# DDR3_Memory_Banks_32-33-34.net
KiCad netlist of a schematic drawn in Altium Designer
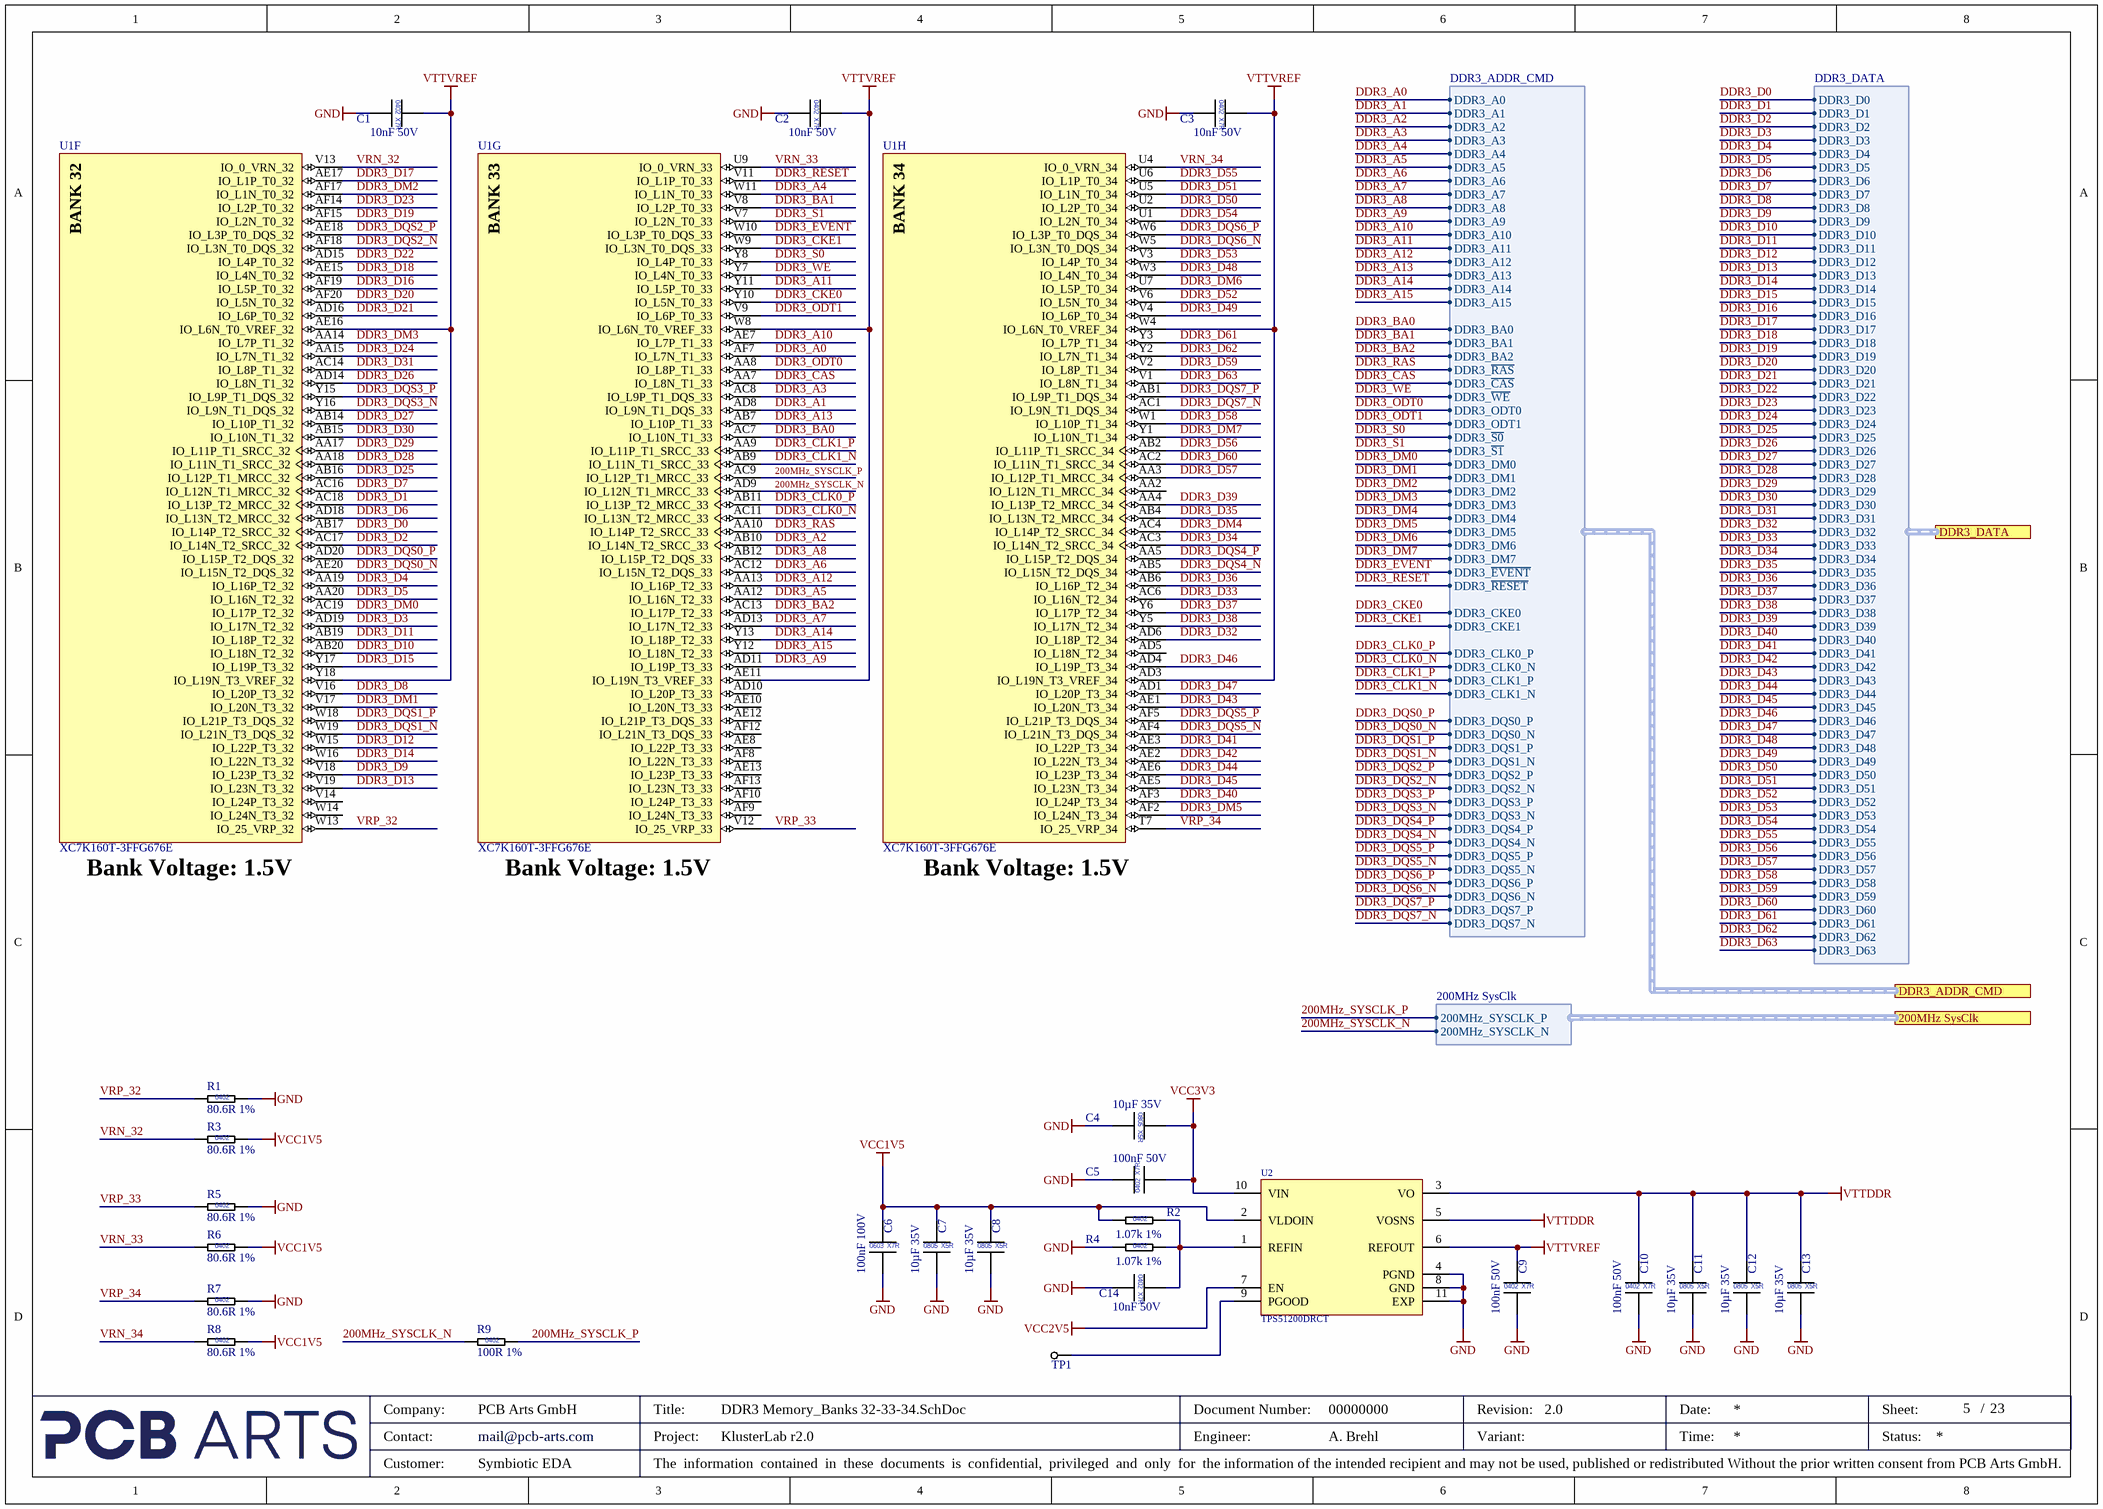
[diagram p0: DDR3 Memory_Banks 32-33-34.SchDoc]

(export (version "E")
  (design (tool "Eeschema 10.0.6"))
  (components
    (comp (ref "C1")
      (value "10nF 50V")
      (footprint "Cap:CAP_0402_L")
      (description "Multilayer Ceramic Capacitors MLCC - SMD/SMT 0402 50VDC")
      (libsource (lib "Cap") (part "CAP_0402_10nF_50V"))
    )
    (comp (ref "C2")
      (value "10nF 50V")
      (footprint "Cap:CAP_0402_L")
      (description "Multilayer Ceramic Capacitors MLCC - SMD/SMT 0402 50VDC")
      (libsource (lib "Cap") (part "CAP_0402_10nF_50V"))
    )
    (comp (ref "C3")
      (value "10nF 50V")
      (footprint "Cap:CAP_0402_L")
      (description "Multilayer Ceramic Capacitors MLCC - SMD/SMT 0402 50VDC")
      (libsource (lib "Cap") (part "CAP_0402_10nF_50V"))
    )
    (comp (ref "C4")
      (value "10µF 35V")
      (footprint "Cap:CAP_0805")
      (description "Multilayer Ceramic Capacitors MLCC - SMD/SMT 0805 35VDC")
      (libsource (lib "Cap") (part "CAP_0805_10µF_35V"))
    )
    (comp (ref "C5")
      (value "100nF 50V")
      (footprint "Cap:CAP_0402_L")
      (description "Multilayer Ceramic Capacitors MLCC - SMD/SMT 0402 50VDC")
      (libsource (lib "") (part "CAP_0402_100nF_50V_1"))
    )
    (comp (ref "C6")
      (value "100nF 100V")
      (footprint "Cap:CAP_0603_L")
      (description "Multilayer Ceramic Capacitors MLCC - SMD/SMT 0603 100VDC")
      (libsource (lib "Cap") (part "CAP_0603_100nF_100V"))
    )
    (comp (ref "C7")
      (value "10µF 35V")
      (footprint "Cap:CAP_0805")
      (description "Multilayer Ceramic Capacitors MLCC - SMD/SMT 0805 35VDC")
      (libsource (lib "Cap") (part "CAP_0805_10µF_35V"))
    )
    (comp (ref "C8")
      (value "10µF 35V")
      (footprint "Cap:CAP_0805")
      (description "Multilayer Ceramic Capacitors MLCC - SMD/SMT 0805 35VDC")
      (libsource (lib "Cap") (part "CAP_0805_10µF_35V"))
    )
    (comp (ref "C9")
      (value "100nF 50V")
      (footprint "Cap:CAP_0402_L")
      (description "Multilayer Ceramic Capacitors MLCC - SMD/SMT 0402 50VDC")
      (libsource (lib "Cap") (part "CAP_0402_100nF_50V"))
    )
    (comp (ref "C10")
      (value "100nF 50V")
      (footprint "Cap:CAP_0402_L")
      (description "Multilayer Ceramic Capacitors MLCC - SMD/SMT 0402 50VDC")
      (libsource (lib "Cap") (part "CAP_0402_100nF_50V"))
    )
    (comp (ref "C11")
      (value "10µF 35V")
      (footprint "Cap:CAP_0805")
      (description "Multilayer Ceramic Capacitors MLCC - SMD/SMT 0805 35VDC")
      (libsource (lib "Cap") (part "CAP_0805_10µF_35V"))
    )
    (comp (ref "C12")
      (value "10µF 35V")
      (footprint "Cap:CAP_0805")
      (description "Multilayer Ceramic Capacitors MLCC - SMD/SMT 0805 35VDC")
      (libsource (lib "Cap") (part "CAP_0805_10µF_35V"))
    )
    (comp (ref "C13")
      (value "10µF 35V")
      (footprint "Cap:CAP_0805")
      (description "Multilayer Ceramic Capacitors MLCC - SMD/SMT 0805 35VDC")
      (libsource (lib "Cap") (part "CAP_0805_10µF_35V"))
    )
    (comp (ref "C14")
      (value "10nF 50V")
      (footprint "Cap:CAP_0402_L")
      (description "Multilayer Ceramic Capacitors MLCC - SMD/SMT 0402 50VDC")
      (libsource (lib "Cap") (part "CAP_0402_10nF_50V"))
    )
    (comp (ref "R1")
      (value "80.6R 1%")
      (footprint "Res:RES_0402_L")
      (description "Thick Film Resistors - SMD 80.6R 1%")
      (libsource (lib "Res") (part "RES_0402_80.6R_1%"))
    )
    (comp (ref "R2")
      (value "1.07k 1%")
      (footprint "Res:RES_0402_L")
      (description "Thick Film Resistors - SMD 1.07kOhm 1%")
      (libsource (lib "Res") (part "RES_0402_1.07k_1%"))
    )
    (comp (ref "R3")
      (value "80.6R 1%")
      (footprint "Res:RES_0402_L")
      (description "Thick Film Resistors - SMD 80.6R 1%")
      (libsource (lib "Res") (part "RES_0402_80.6R_1%"))
    )
    (comp (ref "R4")
      (value "1.07k 1%")
      (footprint "Res:RES_0402_L")
      (description "Thick Film Resistors - SMD 1.07kOhm 1%")
      (libsource (lib "Res") (part "RES_0402_1.07k_1%"))
    )
    (comp (ref "R5")
      (value "80.6R 1%")
      (footprint "Res:RES_0402_L")
      (description "Thick Film Resistors - SMD 80.6R 1%")
      (libsource (lib "Res") (part "RES_0402_80.6R_1%"))
    )
    (comp (ref "R6")
      (value "80.6R 1%")
      (footprint "Res:RES_0402_L")
      (description "Thick Film Resistors - SMD 80.6R 1%")
      (libsource (lib "Res") (part "RES_0402_80.6R_1%"))
    )
    (comp (ref "R7")
      (value "80.6R 1%")
      (footprint "Res:RES_0402_L")
      (description "Thick Film Resistors - SMD 80.6R 1%")
      (libsource (lib "Res") (part "RES_0402_80.6R_1%"))
    )
    (comp (ref "R8")
      (value "80.6R 1%")
      (footprint "Res:RES_0402_L")
      (description "Thick Film Resistors - SMD 80.6R 1%")
      (libsource (lib "Res") (part "RES_0402_80.6R_1%"))
    )
    (comp (ref "R9")
      (value "100R 1%")
      (footprint "Res:RES_0402_L")
      (description "Thick Film Resistors - SMD 100Ohm 1%")
      (libsource (lib "Res") (part "RES_0402_100R_1%"))
    )
    (comp (ref "TP1")
      (value "Testpoint")
      (footprint "Electro_mech:Testpoint 0.8mm")
      (description "Testpoint 0.8mm")
      (libsource (lib "Electro_Mech") (part "Testpoint 0.8mm"))
    )
    (comp (ref "U1")
      (value "XC7K160T-3FFG676E")
      (footprint "Digital:BGA100P2700X2700X317-676N")
      (description "Kintex-7 FPGA, 400 User I/Os, 8 GTX, 676-Ball BGA, Speed Grade 3, Extended Grade, Pb-Free")
      (libsource (lib "Digital") (part "XC7K160T-3FFG676E_Kintex-7 FPGA, 400 User I/Os, 8 GTX, FFG676"))
    )
    (comp (ref "U2")
      (value "TPS51200DRCT")
      (footprint "power:QFN50P300X300X100-11N")
      (description "Sink and Source DDR Termination Regulator")
      (libsource (lib "Power") (part "TPS51200DRCT_Sink and Source DDR Termination Regulator"))
    )
  )
  (nets
    (net (code "5") (name "/200MHz_SYSCLK_N") (class "Default")
      (node (ref "R9") (pin "1") (pinfunction "1_1") (pintype "passive"))
      (node (ref "U1") (pin "AD9") (pinfunction "IO_L12N_T1_MRCC_33_AD9") (pintype "bidirectional"))
    )
    (net (code "6") (name "/200MHz_SYSCLK_P") (class "Default")
      (node (ref "R9") (pin "2") (pinfunction "2_2") (pintype "passive"))
      (node (ref "U1") (pin "AC9") (pinfunction "IO_L12P_T1_MRCC_33_AC9") (pintype "bidirectional"))
    )
    (net (code "7") (name "/DDR3_A0") (class "Default")
      (node (ref "U1") (pin "AF7") (pinfunction "IO_L7N_T1_33_AF7") (pintype "bidirectional"))
    )
    (net (code "8") (name "/DDR3_A1") (class "Default")
      (node (ref "U1") (pin "AD8") (pinfunction "IO_L9N_T1_DQS_33_AD8") (pintype "bidirectional"))
    )
    (net (code "9") (name "/DDR3_A2") (class "Default")
      (node (ref "U1") (pin "AB10") (pinfunction "IO_L14N_T2_SRCC_33_AB10") (pintype "bidirectional"))
    )
    (net (code "10") (name "/DDR3_A3") (class "Default")
      (node (ref "U1") (pin "AC8") (pinfunction "IO_L9P_T1_DQS_33_AC8") (pintype "bidirectional"))
    )
    (net (code "11") (name "/DDR3_A4") (class "Default")
      (node (ref "U1") (pin "W11") (pinfunction "IO_L1N_T0_33_W11") (pintype "bidirectional"))
    )
    (net (code "12") (name "/DDR3_A5") (class "Default")
      (node (ref "U1") (pin "AA12") (pinfunction "IO_L16N_T2_33_AA12") (pintype "bidirectional"))
    )
    (net (code "13") (name "/DDR3_A6") (class "Default")
      (node (ref "U1") (pin "AC12") (pinfunction "IO_L15N_T2_DQS_33_AC12") (pintype "bidirectional"))
    )
    (net (code "14") (name "/DDR3_A7") (class "Default")
      (node (ref "U1") (pin "AD13") (pinfunction "IO_L17N_T2_33_AD13") (pintype "bidirectional"))
    )
    (net (code "15") (name "/DDR3_A8") (class "Default")
      (node (ref "U1") (pin "AB12") (pinfunction "IO_L15P_T2_DQS_33_AB12") (pintype "bidirectional"))
    )
    (net (code "16") (name "/DDR3_A9") (class "Default")
      (node (ref "U1") (pin "AD11") (pinfunction "IO_L19P_T3_33_AD11") (pintype "bidirectional"))
    )
    (net (code "17") (name "/DDR3_A10") (class "Default")
      (node (ref "U1") (pin "AE7") (pinfunction "IO_L7P_T1_33_AE7") (pintype "bidirectional"))
    )
    (net (code "18") (name "/DDR3_A11") (class "Default")
      (node (ref "U1") (pin "Y11") (pinfunction "IO_L5P_T0_33_Y11") (pintype "bidirectional"))
    )
    (net (code "19") (name "/DDR3_A12") (class "Default")
      (node (ref "U1") (pin "AA13") (pinfunction "IO_L16P_T2_33_AA13") (pintype "bidirectional"))
    )
    (net (code "20") (name "/DDR3_A13") (class "Default")
      (node (ref "U1") (pin "AB7") (pinfunction "IO_L10P_T1_33_AB7") (pintype "bidirectional"))
    )
    (net (code "21") (name "/DDR3_A14") (class "Default")
      (node (ref "U1") (pin "Y13") (pinfunction "IO_L18P_T2_33_Y13") (pintype "bidirectional"))
    )
    (net (code "22") (name "/DDR3_A15") (class "Default")
      (node (ref "U1") (pin "Y12") (pinfunction "IO_L18N_T2_33_Y12") (pintype "bidirectional"))
    )
    (net (code "23") (name "/DDR3_BA0") (class "Default")
      (node (ref "U1") (pin "AC7") (pinfunction "IO_L10N_T1_33_AC7") (pintype "bidirectional"))
    )
    (net (code "24") (name "/DDR3_BA1") (class "Default")
      (node (ref "U1") (pin "V8") (pinfunction "IO_L2P_T0_33_V8") (pintype "bidirectional"))
    )
    (net (code "25") (name "/DDR3_BA2") (class "Default")
      (node (ref "U1") (pin "AC13") (pinfunction "IO_L17P_T2_33_AC13") (pintype "bidirectional"))
    )
    (net (code "26") (name "/DDR3_CKE0") (class "Default")
      (node (ref "U1") (pin "Y10") (pinfunction "IO_L5N_T0_33_Y10") (pintype "bidirectional"))
    )
    (net (code "27") (name "/DDR3_CKE1") (class "Default")
      (node (ref "U1") (pin "W9") (pinfunction "IO_L3N_T0_DQS_33_W9") (pintype "bidirectional"))
    )
    (net (code "28") (name "/DDR3_CLK0_N") (class "Default")
      (node (ref "U1") (pin "AC11") (pinfunction "IO_L13N_T2_MRCC_33_AC11") (pintype "bidirectional"))
    )
    (net (code "29") (name "/DDR3_CLK0_P") (class "Default")
      (node (ref "U1") (pin "AB11") (pinfunction "IO_L13P_T2_MRCC_33_AB11") (pintype "bidirectional"))
    )
    (net (code "30") (name "/DDR3_CLK1_N") (class "Default")
      (node (ref "U1") (pin "AB9") (pinfunction "IO_L11N_T1_SRCC_33_AB9") (pintype "bidirectional"))
    )
    (net (code "31") (name "/DDR3_CLK1_P") (class "Default")
      (node (ref "U1") (pin "AA9") (pinfunction "IO_L11P_T1_SRCC_33_AA9") (pintype "bidirectional"))
    )
    (net (code "32") (name "/DDR3_D0") (class "Default")
      (node (ref "U1") (pin "AB17") (pinfunction "IO_L14P_T2_SRCC_32_AB17") (pintype "bidirectional"))
    )
    (net (code "33") (name "/DDR3_D1") (class "Default")
      (node (ref "U1") (pin "AC18") (pinfunction "IO_L13P_T2_MRCC_32_AC18") (pintype "bidirectional"))
    )
    (net (code "34") (name "/DDR3_D2") (class "Default")
      (node (ref "U1") (pin "AC17") (pinfunction "IO_L14N_T2_SRCC_32_AC17") (pintype "bidirectional"))
    )
    (net (code "35") (name "/DDR3_D3") (class "Default")
      (node (ref "U1") (pin "AD19") (pinfunction "IO_L17N_T2_32_AD19") (pintype "bidirectional"))
    )
    (net (code "36") (name "/DDR3_D4") (class "Default")
      (node (ref "U1") (pin "AA19") (pinfunction "IO_L16P_T2_32_AA19") (pintype "bidirectional"))
    )
    (net (code "37") (name "/DDR3_D5") (class "Default")
      (node (ref "U1") (pin "AA20") (pinfunction "IO_L16N_T2_32_AA20") (pintype "bidirectional"))
    )
    (net (code "38") (name "/DDR3_D6") (class "Default")
      (node (ref "U1") (pin "AD18") (pinfunction "IO_L13N_T2_MRCC_32_AD18") (pintype "bidirectional"))
    )
    (net (code "39") (name "/DDR3_D7") (class "Default")
      (node (ref "U1") (pin "AC16") (pinfunction "IO_L12N_T1_MRCC_32_AC16") (pintype "bidirectional"))
    )
    (net (code "40") (name "/DDR3_D8") (class "Default")
      (node (ref "U1") (pin "V16") (pinfunction "IO_L20P_T3_32_V16") (pintype "bidirectional"))
    )
    (net (code "41") (name "/DDR3_D9") (class "Default")
      (node (ref "U1") (pin "V18") (pinfunction "IO_L23P_T3_32_V18") (pintype "bidirectional"))
    )
    (net (code "42") (name "/DDR3_D10") (class "Default")
      (node (ref "U1") (pin "AB20") (pinfunction "IO_L18N_T2_32_AB20") (pintype "bidirectional"))
    )
    (net (code "43") (name "/DDR3_D11") (class "Default")
      (node (ref "U1") (pin "AB19") (pinfunction "IO_L18P_T2_32_AB19") (pintype "bidirectional"))
    )
    (net (code "44") (name "/DDR3_D12") (class "Default")
      (node (ref "U1") (pin "W15") (pinfunction "IO_L22P_T3_32_W15") (pintype "bidirectional"))
    )
    (net (code "45") (name "/DDR3_D13") (class "Default")
      (node (ref "U1") (pin "V19") (pinfunction "IO_L23N_T3_32_V19") (pintype "bidirectional"))
    )
    (net (code "46") (name "/DDR3_D14") (class "Default")
      (node (ref "U1") (pin "W16") (pinfunction "IO_L22N_T3_32_W16") (pintype "bidirectional"))
    )
    (net (code "47") (name "/DDR3_D15") (class "Default")
      (node (ref "U1") (pin "Y17") (pinfunction "IO_L19P_T3_32_Y17") (pintype "bidirectional"))
    )
    (net (code "48") (name "/DDR3_D16") (class "Default")
      (node (ref "U1") (pin "AF19") (pinfunction "IO_L5P_T0_32_AF19") (pintype "bidirectional"))
    )
    (net (code "49") (name "/DDR3_D17") (class "Default")
      (node (ref "U1") (pin "AE17") (pinfunction "IO_L1P_T0_32_AE17") (pintype "bidirectional"))
    )
    (net (code "50") (name "/DDR3_D18") (class "Default")
      (node (ref "U1") (pin "AE15") (pinfunction "IO_L4N_T0_32_AE15") (pintype "bidirectional"))
    )
    (net (code "51") (name "/DDR3_D19") (class "Default")
      (node (ref "U1") (pin "AF15") (pinfunction "IO_L2N_T0_32_AF15") (pintype "bidirectional"))
    )
    (net (code "52") (name "/DDR3_D20") (class "Default")
      (node (ref "U1") (pin "AF20") (pinfunction "IO_L5N_T0_32_AF20") (pintype "bidirectional"))
    )
    (net (code "53") (name "/DDR3_D21") (class "Default")
      (node (ref "U1") (pin "AD16") (pinfunction "IO_L6P_T0_32_AD16") (pintype "bidirectional"))
    )
    (net (code "54") (name "/DDR3_D22") (class "Default")
      (node (ref "U1") (pin "AD15") (pinfunction "IO_L4P_T0_32_AD15") (pintype "bidirectional"))
    )
    (net (code "55") (name "/DDR3_D23") (class "Default")
      (node (ref "U1") (pin "AF14") (pinfunction "IO_L2P_T0_32_AF14") (pintype "bidirectional"))
    )
    (net (code "56") (name "/DDR3_D24") (class "Default")
      (node (ref "U1") (pin "AA15") (pinfunction "IO_L7N_T1_32_AA15") (pintype "bidirectional"))
    )
    (net (code "57") (name "/DDR3_D25") (class "Default")
      (node (ref "U1") (pin "AB16") (pinfunction "IO_L12P_T1_MRCC_32_AB16") (pintype "bidirectional"))
    )
    (net (code "58") (name "/DDR3_D26") (class "Default")
      (node (ref "U1") (pin "AD14") (pinfunction "IO_L8N_T1_32_AD14") (pintype "bidirectional"))
    )
    (net (code "59") (name "/DDR3_D27") (class "Default")
      (node (ref "U1") (pin "AB14") (pinfunction "IO_L10P_T1_32_AB14") (pintype "bidirectional"))
    )
    (net (code "60") (name "/DDR3_D28") (class "Default")
      (node (ref "U1") (pin "AA18") (pinfunction "IO_L11N_T1_SRCC_32_AA18") (pintype "bidirectional"))
    )
    (net (code "61") (name "/DDR3_D29") (class "Default")
      (node (ref "U1") (pin "AA17") (pinfunction "IO_L11P_T1_SRCC_32_AA17") (pintype "bidirectional"))
    )
    (net (code "62") (name "/DDR3_D30") (class "Default")
      (node (ref "U1") (pin "AB15") (pinfunction "IO_L10N_T1_32_AB15") (pintype "bidirectional"))
    )
    (net (code "63") (name "/DDR3_D31") (class "Default")
      (node (ref "U1") (pin "AC14") (pinfunction "IO_L8P_T1_32_AC14") (pintype "bidirectional"))
    )
    (net (code "64") (name "/DDR3_D32") (class "Default")
      (node (ref "U1") (pin "AD6") (pinfunction "IO_L18P_T2_34_AD6") (pintype "bidirectional"))
    )
    (net (code "65") (name "/DDR3_D33") (class "Default")
      (node (ref "U1") (pin "AC6") (pinfunction "IO_L16N_T2_34_AC6") (pintype "bidirectional"))
    )
    (net (code "66") (name "/DDR3_D34") (class "Default")
      (node (ref "U1") (pin "AC3") (pinfunction "IO_L14N_T2_SRCC_34_AC3") (pintype "bidirectional"))
    )
    (net (code "67") (name "/DDR3_D35") (class "Default")
      (node (ref "U1") (pin "AB4") (pinfunction "IO_L13N_T2_MRCC_34_AB4") (pintype "bidirectional"))
    )
    (net (code "68") (name "/DDR3_D36") (class "Default")
      (node (ref "U1") (pin "AB6") (pinfunction "IO_L16P_T2_34_AB6") (pintype "bidirectional"))
    )
    (net (code "69") (name "/DDR3_D37") (class "Default")
      (node (ref "U1") (pin "Y6") (pinfunction "IO_L17P_T2_34_Y6") (pintype "bidirectional"))
    )
    (net (code "70") (name "/DDR3_D38") (class "Default")
      (node (ref "U1") (pin "Y5") (pinfunction "IO_L17N_T2_34_Y5") (pintype "bidirectional"))
    )
    (net (code "71") (name "/DDR3_D39") (class "Default")
      (node (ref "U1") (pin "AA4") (pinfunction "IO_L13P_T2_MRCC_34_AA4") (pintype "bidirectional"))
    )
    (net (code "72") (name "/DDR3_D40") (class "Default")
      (node (ref "U1") (pin "AF3") (pinfunction "IO_L24P_T3_34_AF3") (pintype "bidirectional"))
    )
    (net (code "73") (name "/DDR3_D41") (class "Default")
      (node (ref "U1") (pin "AE3") (pinfunction "IO_L22P_T3_34_AE3") (pintype "bidirectional"))
    )
    (net (code "74") (name "/DDR3_D42") (class "Default")
      (node (ref "U1") (pin "AE2") (pinfunction "IO_L22N_T3_34_AE2") (pintype "bidirectional"))
    )
    (net (code "75") (name "/DDR3_D43") (class "Default")
      (node (ref "U1") (pin "AE1") (pinfunction "IO_L20N_T3_34_AE1") (pintype "bidirectional"))
    )
    (net (code "76") (name "/DDR3_D44") (class "Default")
      (node (ref "U1") (pin "AE6") (pinfunction "IO_L23P_T3_34_AE6") (pintype "bidirectional"))
    )
    (net (code "77") (name "/DDR3_D45") (class "Default")
      (node (ref "U1") (pin "AE5") (pinfunction "IO_L23N_T3_34_AE5") (pintype "bidirectional"))
    )
    (net (code "78") (name "/DDR3_D46") (class "Default")
      (node (ref "U1") (pin "AD4") (pinfunction "IO_L19P_T3_34_AD4") (pintype "bidirectional"))
    )
    (net (code "79") (name "/DDR3_D47") (class "Default")
      (node (ref "U1") (pin "AD1") (pinfunction "IO_L20P_T3_34_AD1") (pintype "bidirectional"))
    )
    (net (code "80") (name "/DDR3_D48") (class "Default")
      (node (ref "U1") (pin "W3") (pinfunction "IO_L4N_T0_34_W3") (pintype "bidirectional"))
    )
    (net (code "81") (name "/DDR3_D49") (class "Default")
      (node (ref "U1") (pin "V4") (pinfunction "IO_L6P_T0_34_V4") (pintype "bidirectional"))
    )
    (net (code "82") (name "/DDR3_D50") (class "Default")
      (node (ref "U1") (pin "U2") (pinfunction "IO_L2P_T0_34_U2") (pintype "bidirectional"))
    )
    (net (code "83") (name "/DDR3_D51") (class "Default")
      (node (ref "U1") (pin "U5") (pinfunction "IO_L1N_T0_34_U5") (pintype "bidirectional"))
    )
    (net (code "84") (name "/DDR3_D52") (class "Default")
      (node (ref "U1") (pin "V6") (pinfunction "IO_L5N_T0_34_V6") (pintype "bidirectional"))
    )
    (net (code "85") (name "/DDR3_D53") (class "Default")
      (node (ref "U1") (pin "V3") (pinfunction "IO_L4P_T0_34_V3") (pintype "bidirectional"))
    )
    (net (code "86") (name "/DDR3_D54") (class "Default")
      (node (ref "U1") (pin "U1") (pinfunction "IO_L2N_T0_34_U1") (pintype "bidirectional"))
    )
    (net (code "87") (name "/DDR3_D55") (class "Default")
      (node (ref "U1") (pin "U6") (pinfunction "IO_L1P_T0_34_U6") (pintype "bidirectional"))
    )
    (net (code "88") (name "/DDR3_D56") (class "Default")
      (node (ref "U1") (pin "AB2") (pinfunction "IO_L11P_T1_SRCC_34_AB2") (pintype "bidirectional"))
    )
    (net (code "89") (name "/DDR3_D57") (class "Default")
      (node (ref "U1") (pin "AA3") (pinfunction "IO_L12P_T1_MRCC_34_AA3") (pintype "bidirectional"))
    )
    (net (code "90") (name "/DDR3_D58") (class "Default")
      (node (ref "U1") (pin "W1") (pinfunction "IO_L10P_T1_34_W1") (pintype "bidirectional"))
    )
    (net (code "91") (name "/DDR3_D59") (class "Default")
      (node (ref "U1") (pin "V2") (pinfunction "IO_L8P_T1_34_V2") (pintype "bidirectional"))
    )
    (net (code "92") (name "/DDR3_D60") (class "Default")
      (node (ref "U1") (pin "AC2") (pinfunction "IO_L11N_T1_SRCC_34_AC2") (pintype "bidirectional"))
    )
    (net (code "93") (name "/DDR3_D61") (class "Default")
      (node (ref "U1") (pin "Y3") (pinfunction "IO_L7P_T1_34_Y3") (pintype "bidirectional"))
    )
    (net (code "94") (name "/DDR3_D62") (class "Default")
      (node (ref "U1") (pin "Y2") (pinfunction "IO_L7N_T1_34_Y2") (pintype "bidirectional"))
    )
    (net (code "95") (name "/DDR3_D63") (class "Default")
      (node (ref "U1") (pin "V1") (pinfunction "IO_L8N_T1_34_V1") (pintype "bidirectional"))
    )
    (net (code "96") (name "/DDR3_DM0") (class "Default")
      (node (ref "U1") (pin "AC19") (pinfunction "IO_L17P_T2_32_AC19") (pintype "bidirectional"))
    )
    (net (code "97") (name "/DDR3_DM1") (class "Default")
      (node (ref "U1") (pin "V17") (pinfunction "IO_L20N_T3_32_V17") (pintype "bidirectional"))
    )
    (net (code "98") (name "/DDR3_DM2") (class "Default")
      (node (ref "U1") (pin "AF17") (pinfunction "IO_L1N_T0_32_AF17") (pintype "bidirectional"))
    )
    (net (code "99") (name "/DDR3_DM3") (class "Default")
      (node (ref "U1") (pin "AA14") (pinfunction "IO_L7P_T1_32_AA14") (pintype "bidirectional"))
    )
    (net (code "100") (name "/DDR3_DM4") (class "Default")
      (node (ref "U1") (pin "AC4") (pinfunction "IO_L14P_T2_SRCC_34_AC4") (pintype "bidirectional"))
    )
    (net (code "101") (name "/DDR3_DM5") (class "Default")
      (node (ref "U1") (pin "AF2") (pinfunction "IO_L24N_T3_34_AF2") (pintype "bidirectional"))
    )
    (net (code "102") (name "/DDR3_DM6") (class "Default")
      (node (ref "U1") (pin "U7") (pinfunction "IO_L5P_T0_34_U7") (pintype "bidirectional"))
    )
    (net (code "103") (name "/DDR3_DM7") (class "Default")
      (node (ref "U1") (pin "Y1") (pinfunction "IO_L10N_T1_34_Y1") (pintype "bidirectional"))
    )
    (net (code "104") (name "/DDR3_DQS0_N") (class "Default")
      (node (ref "U1") (pin "AE20") (pinfunction "IO_L15N_T2_DQS_32_AE20") (pintype "bidirectional"))
    )
    (net (code "105") (name "/DDR3_DQS0_P") (class "Default")
      (node (ref "U1") (pin "AD20") (pinfunction "IO_L15P_T2_DQS_32_AD20") (pintype "bidirectional"))
    )
    (net (code "106") (name "/DDR3_DQS1_N") (class "Default")
      (node (ref "U1") (pin "W19") (pinfunction "IO_L21N_T3_DQS_32_W19") (pintype "bidirectional"))
    )
    (net (code "107") (name "/DDR3_DQS1_P") (class "Default")
      (node (ref "U1") (pin "W18") (pinfunction "IO_L21P_T3_DQS_32_W18") (pintype "bidirectional"))
    )
    (net (code "108") (name "/DDR3_DQS2_N") (class "Default")
      (node (ref "U1") (pin "AF18") (pinfunction "IO_L3N_T0_DQS_32_AF18") (pintype "bidirectional"))
    )
    (net (code "109") (name "/DDR3_DQS2_P") (class "Default")
      (node (ref "U1") (pin "AE18") (pinfunction "IO_L3P_T0_DQS_32_AE18") (pintype "bidirectional"))
    )
    (net (code "110") (name "/DDR3_DQS3_N") (class "Default")
      (node (ref "U1") (pin "Y16") (pinfunction "IO_L9N_T1_DQS_32_Y16") (pintype "bidirectional"))
    )
    (net (code "111") (name "/DDR3_DQS3_P") (class "Default")
      (node (ref "U1") (pin "Y15") (pinfunction "IO_L9P_T1_DQS_32_Y15") (pintype "bidirectional"))
    )
    (net (code "112") (name "/DDR3_DQS4_N") (class "Default")
      (node (ref "U1") (pin "AB5") (pinfunction "IO_L15N_T2_DQS_34_AB5") (pintype "bidirectional"))
    )
    (net (code "113") (name "/DDR3_DQS4_P") (class "Default")
      (node (ref "U1") (pin "AA5") (pinfunction "IO_L15P_T2_DQS_34_AA5") (pintype "bidirectional"))
    )
    (net (code "114") (name "/DDR3_DQS5_N") (class "Default")
      (node (ref "U1") (pin "AF4") (pinfunction "IO_L21N_T3_DQS_34_AF4") (pintype "bidirectional"))
    )
    (net (code "115") (name "/DDR3_DQS5_P") (class "Default")
      (node (ref "U1") (pin "AF5") (pinfunction "IO_L21P_T3_DQS_34_AF5") (pintype "bidirectional"))
    )
    (net (code "116") (name "/DDR3_DQS6_N") (class "Default")
      (node (ref "U1") (pin "W5") (pinfunction "IO_L3N_T0_DQS_34_W5") (pintype "bidirectional"))
    )
    (net (code "117") (name "/DDR3_DQS6_P") (class "Default")
      (node (ref "U1") (pin "W6") (pinfunction "IO_L3P_T0_DQS_34_W6") (pintype "bidirectional"))
    )
    (net (code "118") (name "/DDR3_DQS7_N") (class "Default")
      (node (ref "U1") (pin "AC1") (pinfunction "IO_L9N_T1_DQS_34_AC1") (pintype "bidirectional"))
    )
    (net (code "119") (name "/DDR3_DQS7_P") (class "Default")
      (node (ref "U1") (pin "AB1") (pinfunction "IO_L9P_T1_DQS_34_AB1") (pintype "bidirectional"))
    )
    (net (code "120") (name "/DDR3_ODT0") (class "Default")
      (node (ref "U1") (pin "AA8") (pinfunction "IO_L8P_T1_33_AA8") (pintype "bidirectional"))
    )
    (net (code "121") (name "/DDR3_ODT1") (class "Default")
      (node (ref "U1") (pin "V9") (pinfunction "IO_L6P_T0_33_V9") (pintype "bidirectional"))
    )
    (net (code "122") (name "/DDR3_~{CAS}") (class "Default")
      (node (ref "U1") (pin "AA7") (pinfunction "IO_L8N_T1_33_AA7") (pintype "bidirectional"))
    )
    (net (code "123") (name "/DDR3_~{EVENT}") (class "Default")
      (node (ref "U1") (pin "W10") (pinfunction "IO_L3P_T0_DQS_33_W10") (pintype "bidirectional"))
    )
    (net (code "124") (name "/DDR3_~{RAS}") (class "Default")
      (node (ref "U1") (pin "AA10") (pinfunction "IO_L14P_T2_SRCC_33_AA10") (pintype "bidirectional"))
    )
    (net (code "125") (name "/DDR3_~{RESET}") (class "Default")
      (node (ref "U1") (pin "V11") (pinfunction "IO_L1P_T0_33_V11") (pintype "bidirectional"))
    )
    (net (code "126") (name "/DDR3_~{S0}") (class "Default")
      (node (ref "U1") (pin "Y8") (pinfunction "IO_L4P_T0_33_Y8") (pintype "bidirectional"))
    )
    (net (code "127") (name "/DDR3_~{S1}") (class "Default")
      (node (ref "U1") (pin "V7") (pinfunction "IO_L2N_T0_33_V7") (pintype "bidirectional"))
    )
    (net (code "128") (name "/DDR3_~{WE}") (class "Default")
      (node (ref "U1") (pin "Y7") (pinfunction "IO_L4N_T0_33_Y7") (pintype "bidirectional"))
    )
    (net (code "129") (name "/VRN_32") (class "Default")
      (node (ref "R3") (pin "1") (pinfunction "1_1") (pintype "passive"))
      (node (ref "U1") (pin "V13") (pinfunction "IO_0_VRN_32_V13") (pintype "bidirectional"))
    )
    (net (code "130") (name "/VRN_33") (class "Default")
      (node (ref "R6") (pin "1") (pinfunction "1_1") (pintype "passive"))
      (node (ref "U1") (pin "U9") (pinfunction "IO_0_VRN_33_U9") (pintype "bidirectional"))
    )
    (net (code "131") (name "/VRN_34") (class "Default")
      (node (ref "R8") (pin "1") (pinfunction "1_1") (pintype "passive"))
      (node (ref "U1") (pin "U4") (pinfunction "IO_0_VRN_34_U4") (pintype "bidirectional"))
    )
    (net (code "132") (name "/VRP_32") (class "Default")
      (node (ref "R1") (pin "1") (pinfunction "1_1") (pintype "passive"))
      (node (ref "U1") (pin "W13") (pinfunction "IO_25_VRP_32_W13") (pintype "bidirectional"))
    )
    (net (code "133") (name "/VRP_33") (class "Default")
      (node (ref "R5") (pin "1") (pinfunction "1_1") (pintype "passive"))
      (node (ref "U1") (pin "V12") (pinfunction "IO_25_VRP_33_V12") (pintype "bidirectional"))
    )
    (net (code "134") (name "/VRP_34") (class "Default")
      (node (ref "R7") (pin "1") (pinfunction "1_1") (pintype "passive"))
      (node (ref "U1") (pin "T7") (pinfunction "IO_25_VRP_34_T7") (pintype "bidirectional"))
    )
    (net (code "138") (name "GND") (class "Default")
      (node (ref "C1") (pin "2") (pinfunction "2_2") (pintype "passive"))
      (node (ref "C10") (pin "2") (pinfunction "2_2") (pintype "passive"))
      (node (ref "C11") (pin "2") (pinfunction "2_2") (pintype "passive"))
      (node (ref "C12") (pin "2") (pinfunction "2_2") (pintype "passive"))
      (node (ref "C13") (pin "2") (pinfunction "2_2") (pintype "passive"))
      (node (ref "C14") (pin "2") (pinfunction "2_2") (pintype "passive"))
      (node (ref "C2") (pin "2") (pinfunction "2_2") (pintype "passive"))
      (node (ref "C3") (pin "2") (pinfunction "2_2") (pintype "passive"))
      (node (ref "C4") (pin "2") (pinfunction "2_2") (pintype "passive"))
      (node (ref "C5") (pin "1") (pinfunction "1_1") (pintype "passive"))
      (node (ref "C6") (pin "2") (pinfunction "2_2") (pintype "passive"))
      (node (ref "C7") (pin "2") (pinfunction "2_2") (pintype "passive"))
      (node (ref "C8") (pin "2") (pinfunction "2_2") (pintype "passive"))
      (node (ref "C9") (pin "2") (pinfunction "2_2") (pintype "passive"))
      (node (ref "R1") (pin "2") (pinfunction "2_2") (pintype "passive"))
      (node (ref "R4") (pin "1") (pinfunction "1_1") (pintype "passive"))
      (node (ref "R5") (pin "2") (pinfunction "2_2") (pintype "passive"))
      (node (ref "R7") (pin "2") (pinfunction "2_2") (pintype "passive"))
      (node (ref "U2") (pin "11") (pinfunction "EXP_11") (pintype "passive"))
      (node (ref "U2") (pin "4") (pinfunction "PGND_4") (pintype "passive"))
      (node (ref "U2") (pin "8") (pinfunction "GND_8") (pintype "passive"))
    )
    (net (code "139") (name "Net-(TP1-GND)") (class "Default")
      (node (ref "TP1") (pin "1") (pinfunction "GND_1") (pintype "passive"))
      (node (ref "U2") (pin "9") (pinfunction "PGOOD_9") (pintype "passive"))
    )
    (net (code "140") (name "Net-(U2-REFIN)") (class "Default")
      (node (ref "C14") (pin "1") (pinfunction "1_1") (pintype "passive"))
      (node (ref "R2") (pin "2") (pinfunction "2_2") (pintype "passive"))
      (node (ref "R4") (pin "2") (pinfunction "2_2") (pintype "passive"))
      (node (ref "U2") (pin "1") (pinfunction "REFIN_1") (pintype "passive"))
    )
    (net (code "141") (name "VCC1V5") (class "Default")
      (node (ref "C6") (pin "1") (pinfunction "1_1") (pintype "passive"))
      (node (ref "C7") (pin "1") (pinfunction "1_1") (pintype "passive"))
      (node (ref "C8") (pin "1") (pinfunction "1_1") (pintype "passive"))
      (node (ref "R2") (pin "1") (pinfunction "1_1") (pintype "passive"))
      (node (ref "R3") (pin "2") (pinfunction "2_2") (pintype "passive"))
      (node (ref "R6") (pin "2") (pinfunction "2_2") (pintype "passive"))
      (node (ref "R8") (pin "2") (pinfunction "2_2") (pintype "passive"))
      (node (ref "U2") (pin "2") (pinfunction "VLDOIN_2") (pintype "passive"))
    )
    (net (code "142") (name "VCC2V5") (class "Default")
      (node (ref "U2") (pin "7") (pinfunction "EN_7") (pintype "passive"))
    )
    (net (code "143") (name "VCC3V3") (class "Default")
      (node (ref "C4") (pin "1") (pinfunction "1_1") (pintype "passive"))
      (node (ref "C5") (pin "2") (pinfunction "2_2") (pintype "passive"))
      (node (ref "U2") (pin "10") (pinfunction "VIN_10") (pintype "passive"))
    )
    (net (code "144") (name "VTTDDR") (class "Default")
      (node (ref "C10") (pin "1") (pinfunction "1_1") (pintype "passive"))
      (node (ref "C11") (pin "1") (pinfunction "1_1") (pintype "passive"))
      (node (ref "C12") (pin "1") (pinfunction "1_1") (pintype "passive"))
      (node (ref "C13") (pin "1") (pinfunction "1_1") (pintype "passive"))
      (node (ref "U2") (pin "3") (pinfunction "VO_3") (pintype "passive"))
      (node (ref "U2") (pin "5") (pinfunction "VOSNS_5") (pintype "passive"))
    )
    (net (code "145") (name "VTTVREF") (class "Default")
      (node (ref "C1") (pin "1") (pinfunction "1_1") (pintype "passive"))
      (node (ref "C2") (pin "1") (pinfunction "1_1") (pintype "passive"))
      (node (ref "C3") (pin "1") (pinfunction "1_1") (pintype "passive"))
      (node (ref "C9") (pin "1") (pinfunction "1_1") (pintype "passive"))
      (node (ref "U1") (pin "AD3") (pinfunction "IO_L19N_T3_VREF_34_AD3") (pintype "bidirectional"))
      (node (ref "U1") (pin "AE11") (pinfunction "IO_L19N_T3_VREF_33_AE11") (pintype "bidirectional"))
      (node (ref "U1") (pin "AE16") (pinfunction "IO_L6N_T0_VREF_32_AE16") (pintype "bidirectional"))
      (node (ref "U1") (pin "W4") (pinfunction "IO_L6N_T0_VREF_34_W4") (pintype "bidirectional"))
      (node (ref "U1") (pin "W8") (pinfunction "IO_L6N_T0_VREF_33_W8") (pintype "bidirectional"))
      (node (ref "U1") (pin "Y18") (pinfunction "IO_L19N_T3_VREF_32_Y18") (pintype "bidirectional"))
      (node (ref "U2") (pin "6") (pinfunction "REFOUT_6") (pintype "passive"))
    )
    (net (code "146") (name "unconnected-(U1F-IO_L24N_T3_32-PadW14)") (class "Default")
      (node (ref "U1") (pin "W14") (pinfunction "IO_L24N_T3_32_W14") (pintype "bidirectional"))
    )
    (net (code "147") (name "unconnected-(U1F-IO_L24P_T3_32-PadV14)") (class "Default")
      (node (ref "U1") (pin "V14") (pinfunction "IO_L24P_T3_32_V14") (pintype "bidirectional"))
    )
    (net (code "148") (name "unconnected-(U1G-IO_L20N_T3_33-PadAE10)") (class "Default")
      (node (ref "U1") (pin "AE10") (pinfunction "IO_L20N_T3_33_AE10") (pintype "bidirectional"))
    )
    (net (code "149") (name "unconnected-(U1G-IO_L20P_T3_33-PadAD10)") (class "Default")
      (node (ref "U1") (pin "AD10") (pinfunction "IO_L20P_T3_33_AD10") (pintype "bidirectional"))
    )
    (net (code "150") (name "unconnected-(U1G-IO_L21N_T3_DQS_33-PadAF12)") (class "Default")
      (node (ref "U1") (pin "AF12") (pinfunction "IO_L21N_T3_DQS_33_AF12") (pintype "bidirectional"))
    )
    (net (code "151") (name "unconnected-(U1G-IO_L21P_T3_DQS_33-PadAE12)") (class "Default")
      (node (ref "U1") (pin "AE12") (pinfunction "IO_L21P_T3_DQS_33_AE12") (pintype "bidirectional"))
    )
    (net (code "152") (name "unconnected-(U1G-IO_L22N_T3_33-PadAF8)") (class "Default")
      (node (ref "U1") (pin "AF8") (pinfunction "IO_L22N_T3_33_AF8") (pintype "bidirectional"))
    )
    (net (code "153") (name "unconnected-(U1G-IO_L22P_T3_33-PadAE8)") (class "Default")
      (node (ref "U1") (pin "AE8") (pinfunction "IO_L22P_T3_33_AE8") (pintype "bidirectional"))
    )
    (net (code "154") (name "unconnected-(U1G-IO_L23N_T3_33-PadAF13)") (class "Default")
      (node (ref "U1") (pin "AF13") (pinfunction "IO_L23N_T3_33_AF13") (pintype "bidirectional"))
    )
    (net (code "155") (name "unconnected-(U1G-IO_L23P_T3_33-PadAE13)") (class "Default")
      (node (ref "U1") (pin "AE13") (pinfunction "IO_L23P_T3_33_AE13") (pintype "bidirectional"))
    )
    (net (code "156") (name "unconnected-(U1G-IO_L24N_T3_33-PadAF9)") (class "Default")
      (node (ref "U1") (pin "AF9") (pinfunction "IO_L24N_T3_33_AF9") (pintype "bidirectional"))
    )
    (net (code "157") (name "unconnected-(U1G-IO_L24P_T3_33-PadAF10)") (class "Default")
      (node (ref "U1") (pin "AF10") (pinfunction "IO_L24P_T3_33_AF10") (pintype "bidirectional"))
    )
    (net (code "158") (name "unconnected-(U1H-IO_L12N_T1_MRCC_34-PadAA2)") (class "Default")
      (node (ref "U1") (pin "AA2") (pinfunction "IO_L12N_T1_MRCC_34_AA2") (pintype "bidirectional"))
    )
    (net (code "159") (name "unconnected-(U1H-IO_L18N_T2_34-PadAD5)") (class "Default")
      (node (ref "U1") (pin "AD5") (pinfunction "IO_L18N_T2_34_AD5") (pintype "bidirectional"))
    )
  )
)
